# MPU6050.net
KiCad netlist of a schematic drawn in Altium Designer
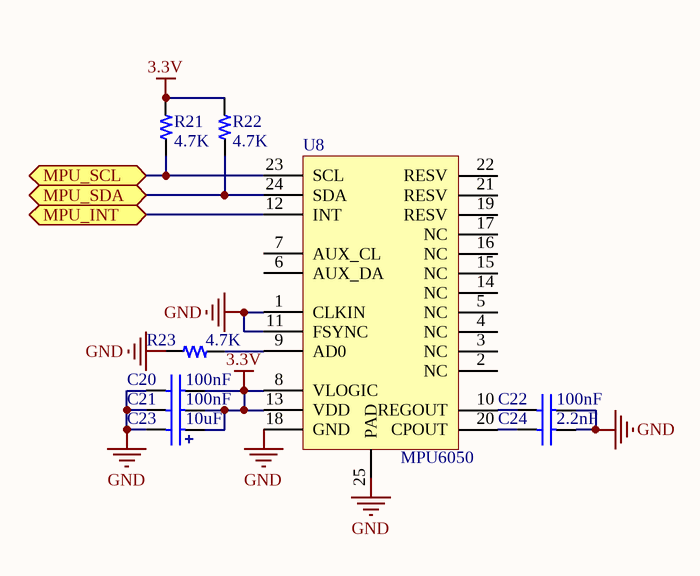
[diagram p0: MPU6050.SchDoc]

(export (version "E")
  (design (tool "Eeschema 10.0.6"))
  (components
    (comp (ref "C20")
      (value "100nF")
      (footprint "dq - 0402")
      (description "Capacitor")
      (fields (field (name "Comment") "Cap") (field (name "PUBLISHER") "Altium Limited"))
      (libsource (lib "weifengdq") (part "DQ_Cap"))
    )
    (comp (ref "C21")
      (value "100nF")
      (footprint "dq - 0402")
      (description "Capacitor")
      (fields (field (name "Comment") "Cap") (field (name "PUBLISHER") "Altium Limited"))
      (libsource (lib "weifengdq") (part "DQ_Cap"))
    )
    (comp (ref "C22")
      (value "100nF")
      (footprint "dq - 0402")
      (description "Capacitor")
      (fields (field (name "Comment") "Cap") (field (name "PUBLISHER") "Altium Limited"))
      (libsource (lib "weifengdq") (part "DQ_Cap"))
    )
    (comp (ref "C23")
      (value "10uF")
      (footprint "3216-18")
      (description "Capacitor")
      (fields (field (name "Comment") "Cap_Pol") (field (name "PUBLISHER") "Altium Limited"))
      (libsource (lib "weifengdq") (part "Cap_Pol"))
    )
    (comp (ref "C24")
      (value "2.2nF")
      (footprint "dq - 0402")
      (description "Capacitor")
      (fields (field (name "Comment") "Cap") (field (name "PUBLISHER") "Altium Limited"))
      (libsource (lib "weifengdq") (part "DQ_Cap"))
    )
    (comp (ref "R21")
      (value "4.7K")
      (footprint "dq - 0402")
      (description "Resistance")
      (fields (field (name "Comment") "Res"))
      (libsource (lib "weifengdq") (part "DQ_Res"))
    )
    (comp (ref "R22")
      (value "4.7K")
      (footprint "dq - 0402")
      (description "Resistance")
      (fields (field (name "Comment") "Res"))
      (libsource (lib "weifengdq") (part "DQ_Res"))
    )
    (comp (ref "R23")
      (value "4.7K")
      (footprint "dq - 0402")
      (description "Resistance")
      (fields (field (name "Comment") "Res"))
      (libsource (lib "weifengdq") (part "DQ_Res"))
    )
    (comp (ref "U8") (value "MPU6050") (footprint "QFN-24") (libsource (lib "weifengdq") (part "MPU6050")))
  )
  (nets
    (net (code "1") (name "/MPU_INT") (class "Default")
      (node (ref "U8") (pin "12") (pinfunction "INT_12") (pintype "passive"))
    )
    (net (code "2") (name "/MPU_SCL") (class "Default")
      (node (ref "R21") (pin "2") (pintype "passive"))
      (node (ref "U8") (pin "23") (pinfunction "SCL_23") (pintype "passive"))
    )
    (net (code "3") (name "/MPU_SDA") (class "Default")
      (node (ref "R22") (pin "2") (pintype "passive"))
      (node (ref "U8") (pin "24") (pinfunction "SDA_24") (pintype "passive"))
    )
    (net (code "4") (name "3.3V") (class "Default")
      (node (ref "C20") (pin "2") (pinfunction "2_2") (pintype "passive"))
      (node (ref "C21") (pin "2") (pinfunction "2_2") (pintype "passive"))
      (node (ref "C23") (pin "1") (pinfunction "1_1") (pintype "passive"))
      (node (ref "R21") (pin "1") (pintype "passive"))
      (node (ref "R22") (pin "1") (pintype "passive"))
      (node (ref "U8") (pin "13") (pinfunction "VDD_13") (pintype "passive"))
      (node (ref "U8") (pin "8") (pinfunction "VLOGIC_8") (pintype "passive"))
    )
    (net (code "5") (name "GND") (class "Default")
      (node (ref "C20") (pin "1") (pinfunction "1_1") (pintype "passive"))
      (node (ref "C21") (pin "1") (pinfunction "1_1") (pintype "passive"))
      (node (ref "C22") (pin "2") (pinfunction "2_2") (pintype "passive"))
      (node (ref "C23") (pin "2") (pinfunction "2_2") (pintype "passive"))
      (node (ref "C24") (pin "2") (pinfunction "2_2") (pintype "passive"))
      (node (ref "R23") (pin "1") (pintype "passive"))
      (node (ref "U8") (pin "1") (pinfunction "CLKIN_1") (pintype "passive"))
      (node (ref "U8") (pin "11") (pinfunction "FSYNC_11") (pintype "passive"))
      (node (ref "U8") (pin "18") (pinfunction "GND_18") (pintype "passive"))
      (node (ref "U8") (pin "25") (pinfunction "PAD_25") (pintype "passive"))
    )
    (net (code "6") (name "Net-(U8-AD0)") (class "Default")
      (node (ref "R23") (pin "2") (pintype "passive"))
      (node (ref "U8") (pin "9") (pinfunction "AD0_9") (pintype "passive"))
    )
    (net (code "7") (name "Net-(U8-CPOUT)") (class "Default")
      (node (ref "C24") (pin "1") (pinfunction "1_1") (pintype "passive"))
      (node (ref "U8") (pin "20") (pinfunction "CPOUT_20") (pintype "passive"))
    )
    (net (code "8") (name "Net-(U8-REGOUT)") (class "Default")
      (node (ref "C22") (pin "1") (pinfunction "1_1") (pintype "passive"))
      (node (ref "U8") (pin "10") (pinfunction "REGOUT_10") (pintype "passive"))
    )
    (net (code "9") (name "unconnected-(U8-AUX_CL-Pad7)") (class "Default")
      (node (ref "U8") (pin "7") (pinfunction "AUX_CL_7") (pintype "passive"))
    )
    (net (code "10") (name "unconnected-(U8-AUX_DA-Pad6)") (class "Default")
      (node (ref "U8") (pin "6") (pinfunction "AUX_DA_6") (pintype "passive"))
    )
    (net (code "11") (name "unconnected-(U8-NC-Pad2)") (class "Default")
      (node (ref "U8") (pin "2") (pinfunction "NC_2") (pintype "passive"))
    )
    (net (code "12") (name "unconnected-(U8-NC-Pad3)") (class "Default")
      (node (ref "U8") (pin "3") (pinfunction "NC_3") (pintype "passive"))
    )
    (net (code "13") (name "unconnected-(U8-NC-Pad4)") (class "Default")
      (node (ref "U8") (pin "4") (pinfunction "NC_4") (pintype "passive"))
    )
    (net (code "14") (name "unconnected-(U8-NC-Pad5)") (class "Default")
      (node (ref "U8") (pin "5") (pinfunction "NC_5") (pintype "passive"))
    )
    (net (code "15") (name "unconnected-(U8-NC-Pad14)") (class "Default")
      (node (ref "U8") (pin "14") (pinfunction "NC_14") (pintype "passive"))
    )
    (net (code "16") (name "unconnected-(U8-NC-Pad15)") (class "Default")
      (node (ref "U8") (pin "15") (pinfunction "NC_15") (pintype "passive"))
    )
    (net (code "17") (name "unconnected-(U8-NC-Pad16)") (class "Default")
      (node (ref "U8") (pin "16") (pinfunction "NC_16") (pintype "passive"))
    )
    (net (code "18") (name "unconnected-(U8-NC-Pad17)") (class "Default")
      (node (ref "U8") (pin "17") (pinfunction "NC_17") (pintype "passive"))
    )
    (net (code "19") (name "unconnected-(U8-RESV-Pad19)") (class "Default")
      (node (ref "U8") (pin "19") (pinfunction "RESV_19") (pintype "passive"))
    )
    (net (code "20") (name "unconnected-(U8-RESV-Pad21)") (class "Default")
      (node (ref "U8") (pin "21") (pinfunction "RESV_21") (pintype "passive"))
    )
    (net (code "21") (name "unconnected-(U8-RESV-Pad22)") (class "Default")
      (node (ref "U8") (pin "22") (pinfunction "RESV_22") (pintype "passive"))
    )
  )
)
